# SevenSegmentDisplay.net
KiCad netlist of a schematic drawn in EAGLE
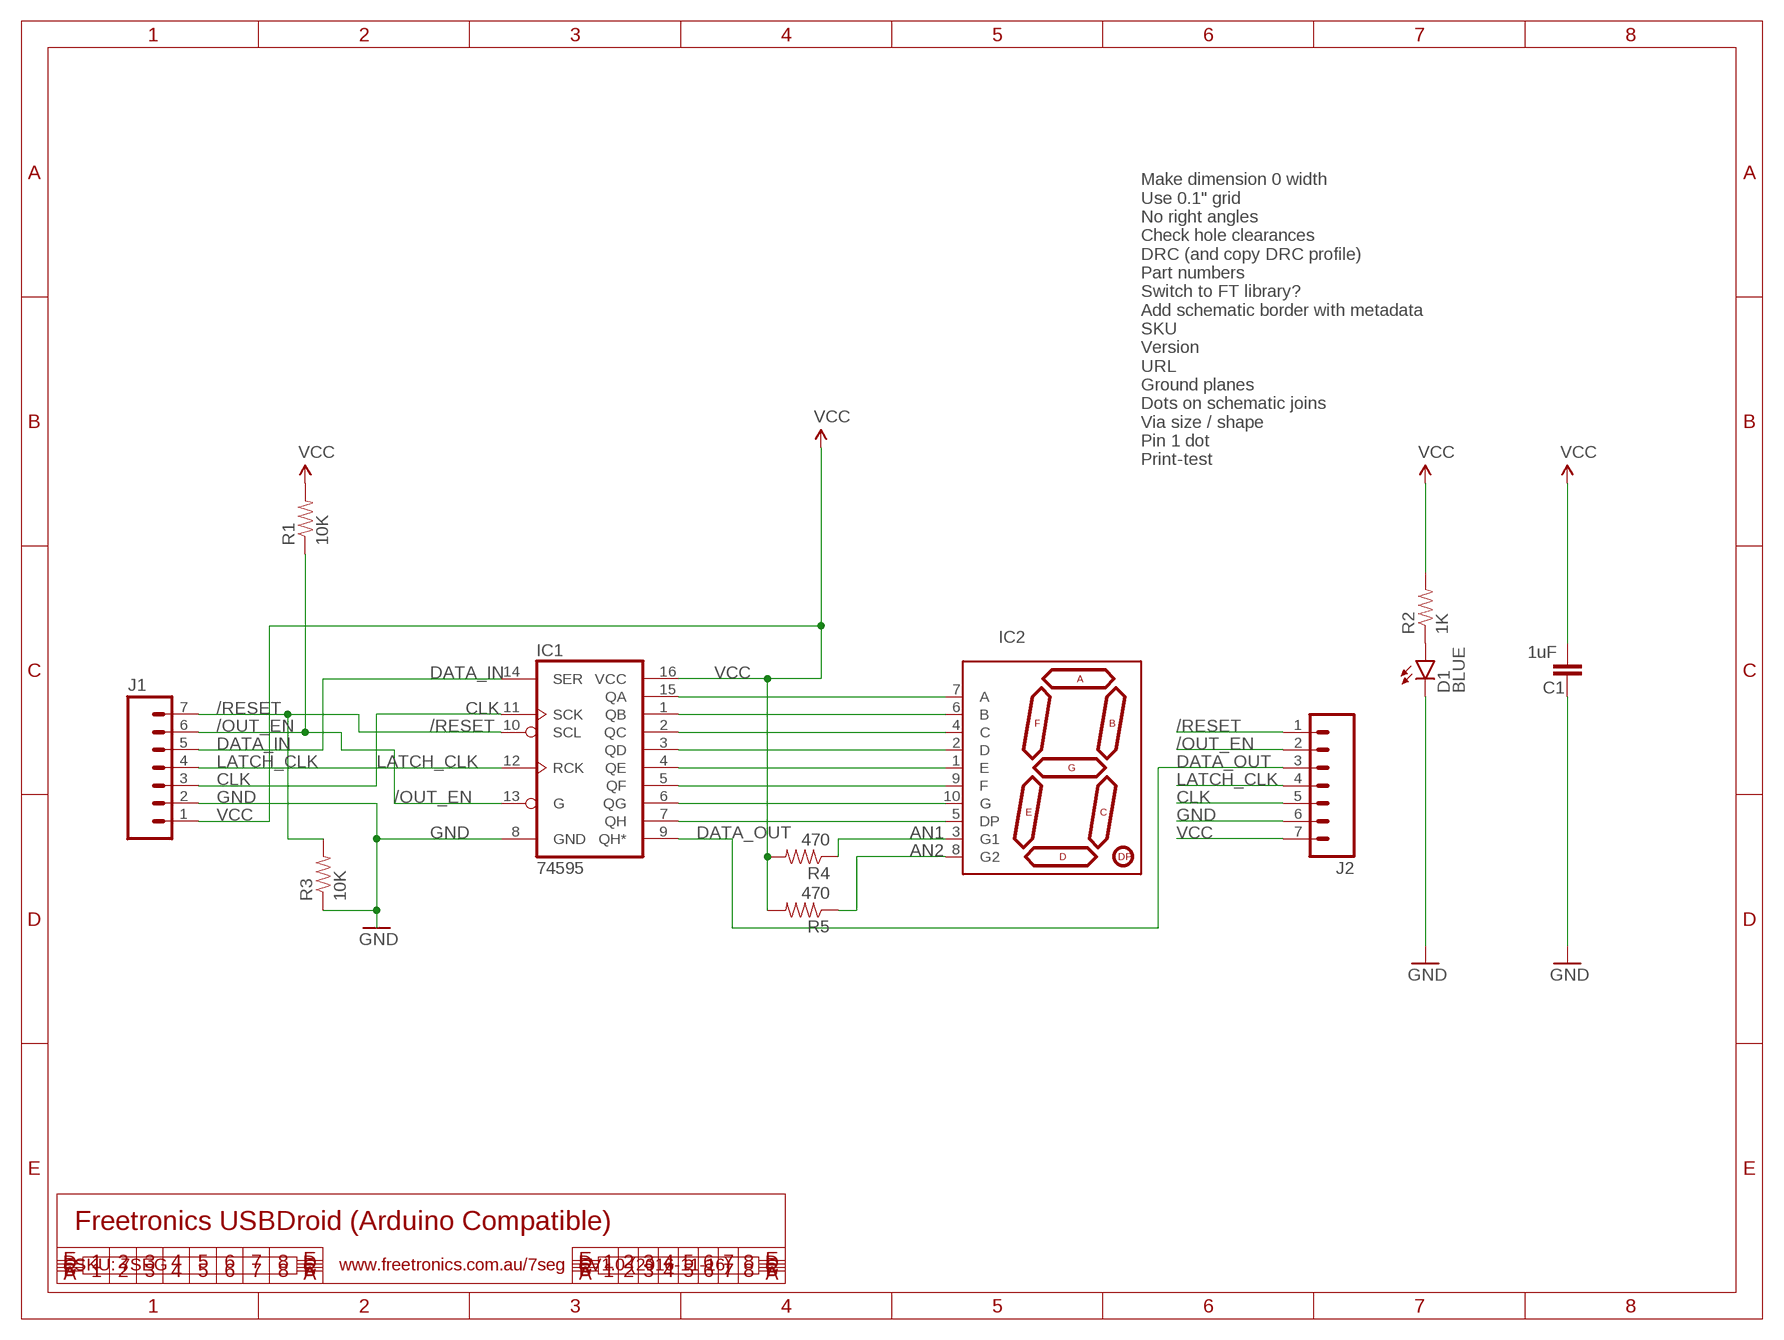
[diagram p0: schematic, sheet 1]

(export (version "E")
  (design (tool "Eeschema 10.0.6"))
  (components
    (comp (ref "C1")
      (value "1uF")
      (footprint "eagle-import:0603-CAP")
      (libsource (lib "eagle-import") (part "CAP0603-CAP"))
    )
    (comp (ref "D1")
      (value "BLUE")
      (footprint "eagle-import:LED-0603")
      (libsource (lib "eagle-import") (part "LED-BLUE0603"))
    )
    (comp (ref "IC1")
      (value "74595")
      (footprint "eagle-import:TSSOP16")
      (libsource (lib "eagle-import") (part "74595"))
    )
    (comp (ref "IC2")
      (value "7-SEGMENT-DISPLAYPTH")
      (footprint "eagle-import:7-SEGMENT-DISPLAY")
      (libsource (lib "eagle-import") (part "7-SEGMENT-DISPLAYPTH"))
    )
    (comp (ref "J1")
      (value "M07")
      (footprint "eagle-import:1X07")
      (libsource (lib "eagle-import") (part "M07"))
    )
    (comp (ref "J2")
      (value "M07")
      (footprint "eagle-import:1X07")
      (libsource (lib "eagle-import") (part "M07"))
    )
    (comp (ref "R1")
      (value "10K")
      (footprint "eagle-import:0603-RES")
      (libsource (lib "eagle-import") (part "RESISTOR0603-RES"))
    )
    (comp (ref "R2")
      (value "1K")
      (footprint "eagle-import:0603-RES")
      (libsource (lib "eagle-import") (part "RESISTOR0603-RES"))
    )
    (comp (ref "R3")
      (value "10K")
      (footprint "eagle-import:0603-RES")
      (libsource (lib "eagle-import") (part "RESISTOR0603"))
    )
    (comp (ref "R4")
      (value "470")
      (footprint "eagle-import:0603-RES")
      (libsource (lib "eagle-import") (part "RESISTOR0603"))
    )
    (comp (ref "R5")
      (value "470")
      (footprint "eagle-import:0603-RES")
      (libsource (lib "eagle-import") (part "RESISTOR0603"))
    )
  )
  (nets
    (net (code "1") (name "/AN1") (class "Default")
      (node (ref "IC2") (pin "3") (pinfunction "G1_3") (pintype "bidirectional"))
      (node (ref "R4") (pin "1") (pinfunction "1_1") (pintype "passive"))
    )
    (net (code "2") (name "/AN2") (class "Default")
      (node (ref "IC2") (pin "8") (pinfunction "G2_8") (pintype "bidirectional"))
      (node (ref "R5") (pin "1") (pinfunction "1_1") (pintype "passive"))
    )
    (net (code "3") (name "/CLK") (class "Default")
      (node (ref "IC1") (pin "11") (pinfunction "SCK_11") (pintype "input"))
      (node (ref "J1") (pin "3") (pinfunction "3_3") (pintype "passive"))
      (node (ref "J2") (pin "5") (pinfunction "5_5") (pintype "passive"))
    )
    (net (code "4") (name "/DATA_IN") (class "Default")
      (node (ref "IC1") (pin "14") (pinfunction "SER_14") (pintype "input"))
      (node (ref "J1") (pin "5") (pinfunction "5_5") (pintype "passive"))
    )
    (net (code "5") (name "/DATA_OUT") (class "Default")
      (node (ref "IC1") (pin "9") (pinfunction "QH*_9") (pintype "tri_state"))
      (node (ref "J2") (pin "3") (pinfunction "3_3") (pintype "passive"))
    )
    (net (code "6") (name "/LATCH_CLK") (class "Default")
      (node (ref "IC1") (pin "12") (pinfunction "RCK_12") (pintype "input"))
      (node (ref "J1") (pin "4") (pinfunction "4_4") (pintype "passive"))
      (node (ref "J2") (pin "4") (pinfunction "4_4") (pintype "passive"))
    )
    (net (code "7") (name "/{slash}OUT_EN") (class "Default")
      (node (ref "IC1") (pin "13") (pinfunction "G_13") (pintype "input"))
      (node (ref "J1") (pin "6") (pinfunction "6_6") (pintype "passive"))
      (node (ref "J2") (pin "2") (pinfunction "2_2") (pintype "passive"))
      (node (ref "R1") (pin "1") (pinfunction "1_1") (pintype "passive"))
    )
    (net (code "8") (name "/{slash}RESET") (class "Default")
      (node (ref "IC1") (pin "10") (pinfunction "SCL_10") (pintype "input"))
      (node (ref "J1") (pin "7") (pinfunction "7_7") (pintype "passive"))
      (node (ref "J2") (pin "1") (pinfunction "1_1") (pintype "passive"))
      (node (ref "R3") (pin "2") (pinfunction "2_2") (pintype "passive"))
    )
    (net (code "9") (name "GND") (class "Default")
      (node (ref "C1") (pin "1") (pinfunction "1_1") (pintype "passive"))
      (node (ref "D1") (pin "C") (pinfunction "C_C") (pintype "passive"))
      (node (ref "IC1") (pin "8") (pinfunction "GND_8") (pintype "power_in"))
      (node (ref "J1") (pin "2") (pinfunction "2_2") (pintype "passive"))
      (node (ref "J2") (pin "6") (pinfunction "6_6") (pintype "passive"))
      (node (ref "R3") (pin "1") (pinfunction "1_1") (pintype "passive"))
    )
    (net (code "10") (name "Net-(D1-PadA)") (class "Default")
      (node (ref "D1") (pin "A") (pinfunction "A_A") (pintype "passive"))
      (node (ref "R2") (pin "1") (pinfunction "1_1") (pintype "passive"))
    )
    (net (code "11") (name "Net-(IC1-QA)") (class "Default")
      (node (ref "IC1") (pin "15") (pinfunction "QA_15") (pintype "tri_state"))
      (node (ref "IC2") (pin "7") (pinfunction "A_7") (pintype "bidirectional"))
    )
    (net (code "12") (name "Net-(IC1-QB)") (class "Default")
      (node (ref "IC1") (pin "1") (pinfunction "QB_1") (pintype "tri_state"))
      (node (ref "IC2") (pin "6") (pinfunction "B_6") (pintype "bidirectional"))
    )
    (net (code "13") (name "Net-(IC1-QC)") (class "Default")
      (node (ref "IC1") (pin "2") (pinfunction "QC_2") (pintype "tri_state"))
      (node (ref "IC2") (pin "4") (pinfunction "C_4") (pintype "bidirectional"))
    )
    (net (code "14") (name "Net-(IC1-QD)") (class "Default")
      (node (ref "IC1") (pin "3") (pinfunction "QD_3") (pintype "tri_state"))
      (node (ref "IC2") (pin "2") (pinfunction "D_2") (pintype "bidirectional"))
    )
    (net (code "15") (name "Net-(IC1-QE)") (class "Default")
      (node (ref "IC1") (pin "4") (pinfunction "QE_4") (pintype "tri_state"))
      (node (ref "IC2") (pin "1") (pinfunction "E_1") (pintype "bidirectional"))
    )
    (net (code "16") (name "Net-(IC1-QF)") (class "Default")
      (node (ref "IC1") (pin "5") (pinfunction "QF_5") (pintype "tri_state"))
      (node (ref "IC2") (pin "9") (pinfunction "F_9") (pintype "bidirectional"))
    )
    (net (code "17") (name "Net-(IC1-QG)") (class "Default")
      (node (ref "IC1") (pin "6") (pinfunction "QG_6") (pintype "tri_state"))
      (node (ref "IC2") (pin "10") (pinfunction "G_10") (pintype "bidirectional"))
    )
    (net (code "18") (name "Net-(IC1-QH)") (class "Default")
      (node (ref "IC1") (pin "7") (pinfunction "QH_7") (pintype "tri_state"))
      (node (ref "IC2") (pin "5") (pinfunction "DP_5") (pintype "bidirectional"))
    )
    (net (code "19") (name "VCC") (class "Default")
      (node (ref "C1") (pin "2") (pinfunction "2_2") (pintype "passive"))
      (node (ref "IC1") (pin "16") (pinfunction "VCC_16") (pintype "power_in"))
      (node (ref "J1") (pin "1") (pinfunction "1_1") (pintype "passive"))
      (node (ref "J2") (pin "7") (pinfunction "7_7") (pintype "passive"))
      (node (ref "R1") (pin "2") (pinfunction "2_2") (pintype "passive"))
      (node (ref "R2") (pin "2") (pinfunction "2_2") (pintype "passive"))
      (node (ref "R4") (pin "2") (pinfunction "2_2") (pintype "passive"))
      (node (ref "R5") (pin "2") (pinfunction "2_2") (pintype "passive"))
    )
  )
)
